# Sheet.net
KiCad netlist of a schematic drawn in Altium Designer
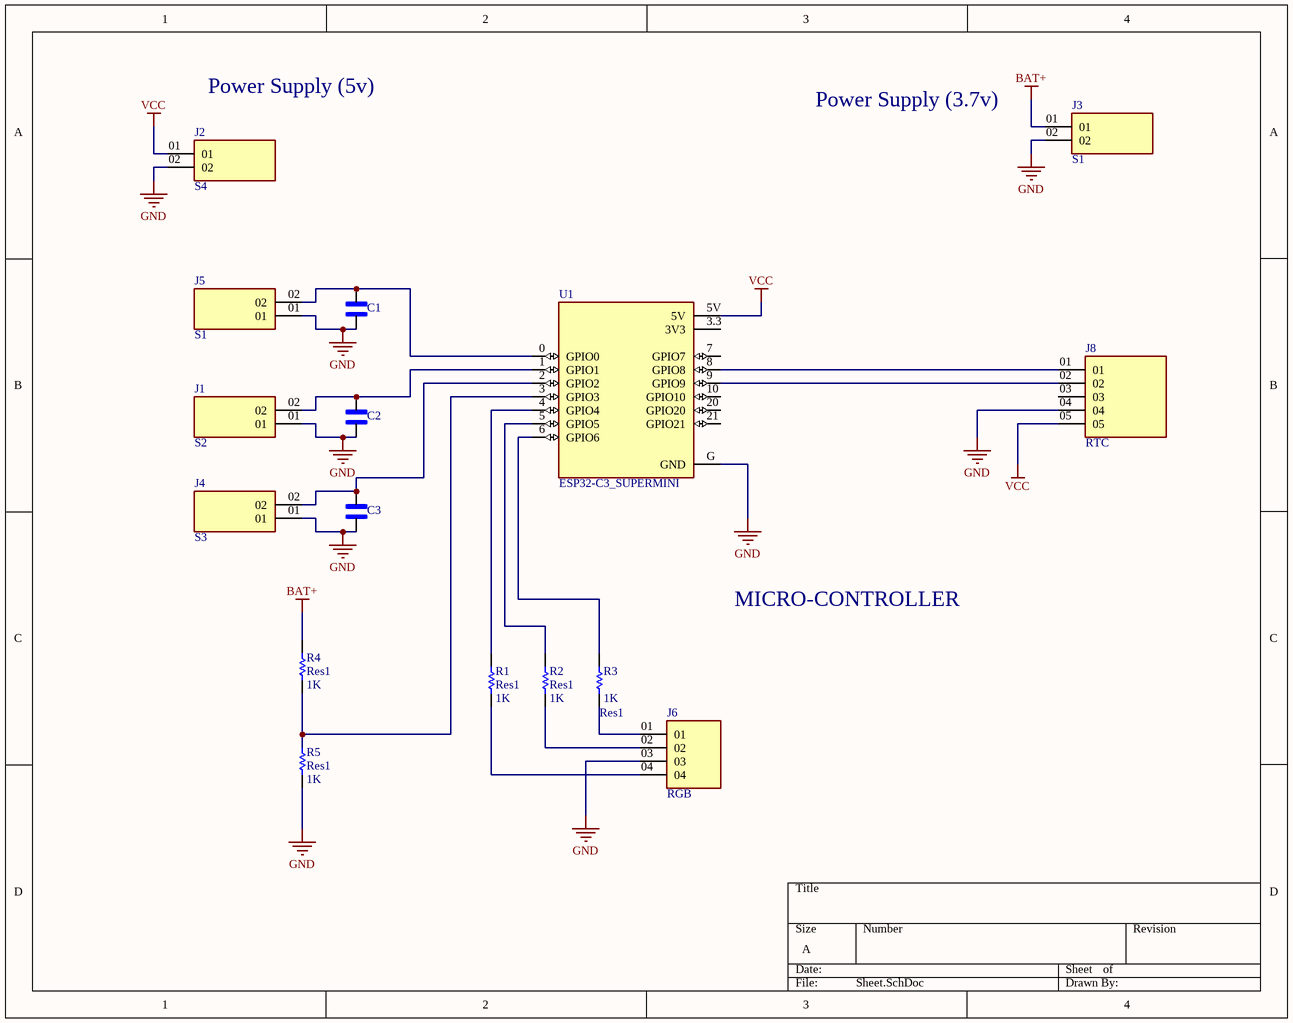
[diagram p0: Sheet.SchDoc]

(export (version "E")
  (design (tool "Eeschema 10.0.6"))
  (components
    (comp (ref "C1")
      (value "C315C470J1G5TA")
      (footprint "CAPRR254W54L381T254H466")
      (description "Capacitor: ceramic; MLCC, monolithic; 47pF; 100V; C0G; Â±5%; THT")
      (fields (field (name "MF") "KEMET"))
      (libsource (lib "C315C470J1G5TA") (part "C315C470J1G5TA"))
    )
    (comp (ref "C2")
      (value "C315C470J1G5TA")
      (footprint "CAPRR254W54L381T254H466")
      (description "Capacitor: ceramic; MLCC, monolithic; 47pF; 100V; C0G; Â±5%; THT")
      (fields (field (name "MF") "KEMET"))
      (libsource (lib "C315C470J1G5TA") (part "C315C470J1G5TA"))
    )
    (comp (ref "C3")
      (value "C315C470J1G5TA")
      (footprint "CAPRR254W54L381T254H466")
      (description "Capacitor: ceramic; MLCC, monolithic; 47pF; 100V; C0G; Â±5%; THT")
      (fields (field (name "MF") "KEMET"))
      (libsource (lib "C315C470J1G5TA") (part "C315C470J1G5TA"))
    )
    (comp (ref "J1")
      (value "S2")
      (footprint "SAMTEC_TSW-202-07-T-S:SAMTEC_TSW-202-07-T-S")
      (fields (field (name "MP") "TSW-202-07-T-S"))
      (libsource (lib "TSW-202-07-T-S") (part "TSW-202-07-T-S"))
    )
    (comp (ref "J2")
      (value "S4")
      (footprint "SAMTEC_TSW-202-07-T-S:SAMTEC_TSW-202-07-T-S")
      (fields (field (name "MP") "TSW-202-07-T-S"))
      (libsource (lib "") (part "TSW-202-07-T-S_1"))
    )
    (comp (ref "J3")
      (value "S1")
      (footprint "SAMTEC_TSW-202-07-T-S:SAMTEC_TSW-202-07-T-S")
      (fields (field (name "MP") "TSW-202-07-T-S"))
      (libsource (lib "") (part "TSW-202-07-T-S_1"))
    )
    (comp (ref "J4")
      (value "S3")
      (footprint "SAMTEC_TSW-202-07-T-S:SAMTEC_TSW-202-07-T-S")
      (fields (field (name "MP") "TSW-202-07-T-S"))
      (libsource (lib "TSW-202-07-T-S") (part "TSW-202-07-T-S"))
    )
    (comp (ref "J5")
      (value "S1")
      (footprint "SAMTEC_TSW-202-07-T-S:SAMTEC_TSW-202-07-T-S")
      (fields (field (name "MP") "TSW-202-07-T-S"))
      (libsource (lib "TSW-202-07-T-S") (part "TSW-202-07-T-S"))
    )
    (comp (ref "J6")
      (value "RGB")
      (footprint "SAMTEC_MTLW-104-X-X-S-X")
      (fields (field (name "MF") "{'manufacturer': u'Samtec Inc.'}") (field (name "MP") "MTLW-104-X-X-S-X"))
      (libsource (lib "MTLW-104-X-X-S-X") (part "MTLW-104-X-X-S-X"))
    )
    (comp (ref "J8")
      (value "RTC")
      (footprint "SAMTEC_TSW-105-23-L-S")
      (description "Connector Header Through Hole 5 position 0.100 (2.54mm)")
      (fields (field (name "MF") "Samtec") (field (name "MP") "TSW-105-23-L-S"))
      (libsource (lib "TSW-105-23-L-S") (part "TSW-105-23-L-S"))
    )
    (comp (ref "R1")
      (value "Res1")
      (footprint "AXIAL-0.3")
      (description "Resistor")
      (fields (field (name "ALTIUM_VALUE") "1K") (field (name "PUBLISHER") "Altium Limited"))
      (libsource (lib "Miscellaneous Devices") (part "Res1"))
    )
    (comp (ref "R2")
      (value "Res1")
      (footprint "AXIAL-0.3")
      (description "Resistor")
      (fields (field (name "ALTIUM_VALUE") "1K") (field (name "PUBLISHER") "Altium Limited"))
      (libsource (lib "Miscellaneous Devices") (part "Res1"))
    )
    (comp (ref "R3")
      (value "Res1")
      (footprint "AXIAL-0.3")
      (description "Resistor")
      (fields (field (name "ALTIUM_VALUE") "1K") (field (name "PUBLISHER") "Altium Limited"))
      (libsource (lib "Miscellaneous Devices") (part "Res1"))
    )
    (comp (ref "R4")
      (value "Res1")
      (footprint "AXIAL-0.3")
      (description "Resistor")
      (fields (field (name "ALTIUM_VALUE") "1K") (field (name "PUBLISHER") "Altium Limited"))
      (libsource (lib "Miscellaneous Devices") (part "Res1"))
    )
    (comp (ref "R5")
      (value "Res1")
      (footprint "AXIAL-0.3")
      (description "Resistor")
      (fields (field (name "ALTIUM_VALUE") "1K") (field (name "PUBLISHER") "Altium Limited"))
      (libsource (lib "Miscellaneous Devices") (part "Res1"))
    )
    (comp (ref "U1")
      (value "ESP32-C3_SUPERMINI")
      (footprint "MODULE_ESP32-C3_SUPERMINI")
      (description "Super tiny ESP32-C3 board")
      (fields (field (name "MF") "Espressif Systems") (field (name "MP") "ESP32-C3 SuperMini"))
      (libsource (lib "ESP32-C3_SUPERMINI") (part "ESP32-C3_SUPERMINI"))
    )
  )
  (nets
    (net (code "1") (name "BAT+") (class "Default")
      (node (ref "J3") (pin "01") (pinfunction "01_01") (pintype "passive"))
      (node (ref "R4") (pin "1") (pinfunction "1_1") (pintype "passive"))
    )
    (net (code "2") (name "GND") (class "Default")
      (node (ref "C1") (pin "1") (pinfunction "1_1") (pintype "passive"))
      (node (ref "C2") (pin "1") (pinfunction "1_1") (pintype "passive"))
      (node (ref "C3") (pin "1") (pinfunction "1_1") (pintype "passive"))
      (node (ref "J1") (pin "01") (pinfunction "01_01") (pintype "passive"))
      (node (ref "J2") (pin "02") (pinfunction "02_02") (pintype "passive"))
      (node (ref "J3") (pin "02") (pinfunction "02_02") (pintype "passive"))
      (node (ref "J4") (pin "01") (pinfunction "01_01") (pintype "passive"))
      (node (ref "J5") (pin "01") (pinfunction "01_01") (pintype "passive"))
      (node (ref "J6") (pin "03") (pinfunction "03_03") (pintype "passive"))
      (node (ref "J8") (pin "04") (pinfunction "04_04") (pintype "passive"))
      (node (ref "R5") (pin "2") (pinfunction "2_2") (pintype "passive"))
      (node (ref "U1") (pin "G") (pinfunction "GND_G") (pintype "power_in"))
    )
    (net (code "3") (name "Net-(J6-Pad01)") (class "Default")
      (node (ref "J6") (pin "01") (pinfunction "01_01") (pintype "passive"))
      (node (ref "R3") (pin "2") (pinfunction "2_2") (pintype "passive"))
    )
    (net (code "4") (name "Net-(J6-Pad02)") (class "Default")
      (node (ref "J6") (pin "02") (pinfunction "02_02") (pintype "passive"))
      (node (ref "R2") (pin "2") (pinfunction "2_2") (pintype "passive"))
    )
    (net (code "5") (name "Net-(J6-Pad04)") (class "Default")
      (node (ref "J6") (pin "04") (pinfunction "04_04") (pintype "passive"))
      (node (ref "R1") (pin "2") (pinfunction "2_2") (pintype "passive"))
    )
    (net (code "6") (name "Net-(U1-GPIO0)") (class "Default")
      (node (ref "C1") (pin "2") (pinfunction "2_2") (pintype "passive"))
      (node (ref "J5") (pin "02") (pinfunction "02_02") (pintype "passive"))
      (node (ref "U1") (pin "0") (pinfunction "GPIO0_0") (pintype "bidirectional"))
    )
    (net (code "7") (name "Net-(U1-GPIO1)") (class "Default")
      (node (ref "C2") (pin "2") (pinfunction "2_2") (pintype "passive"))
      (node (ref "J1") (pin "02") (pinfunction "02_02") (pintype "passive"))
      (node (ref "U1") (pin "1") (pinfunction "GPIO1_1") (pintype "bidirectional"))
    )
    (net (code "8") (name "Net-(U1-GPIO2)") (class "Default")
      (node (ref "C3") (pin "2") (pinfunction "2_2") (pintype "passive"))
      (node (ref "J4") (pin "02") (pinfunction "02_02") (pintype "passive"))
      (node (ref "U1") (pin "2") (pinfunction "GPIO2_2") (pintype "bidirectional"))
    )
    (net (code "9") (name "Net-(U1-GPIO3)") (class "Default")
      (node (ref "R4") (pin "2") (pinfunction "2_2") (pintype "passive"))
      (node (ref "R5") (pin "1") (pinfunction "1_1") (pintype "passive"))
      (node (ref "U1") (pin "3") (pinfunction "GPIO3_3") (pintype "bidirectional"))
    )
    (net (code "10") (name "Net-(U1-GPIO4)") (class "Default")
      (node (ref "R1") (pin "1") (pinfunction "1_1") (pintype "passive"))
      (node (ref "U1") (pin "4") (pinfunction "GPIO4_4") (pintype "bidirectional"))
    )
    (net (code "11") (name "Net-(U1-GPIO5)") (class "Default")
      (node (ref "R2") (pin "1") (pinfunction "1_1") (pintype "passive"))
      (node (ref "U1") (pin "5") (pinfunction "GPIO5_5") (pintype "bidirectional"))
    )
    (net (code "12") (name "Net-(U1-GPIO6)") (class "Default")
      (node (ref "R3") (pin "1") (pinfunction "1_1") (pintype "passive"))
      (node (ref "U1") (pin "6") (pinfunction "GPIO6_6") (pintype "bidirectional"))
    )
    (net (code "13") (name "Net-(U1-GPIO8)") (class "Default")
      (node (ref "J8") (pin "01") (pinfunction "01_01") (pintype "passive"))
      (node (ref "U1") (pin "8") (pinfunction "GPIO8_8") (pintype "bidirectional"))
    )
    (net (code "14") (name "Net-(U1-GPIO9)") (class "Default")
      (node (ref "J8") (pin "02") (pinfunction "02_02") (pintype "passive"))
      (node (ref "U1") (pin "9") (pinfunction "GPIO9_9") (pintype "bidirectional"))
    )
    (net (code "15") (name "VCC") (class "Default")
      (node (ref "J2") (pin "01") (pinfunction "01_01") (pintype "passive"))
      (node (ref "J8") (pin "05") (pinfunction "05_05") (pintype "passive"))
      (node (ref "U1") (pin "5V") (pinfunction "5V_5V") (pintype "power_in"))
    )
    (net (code "16") (name "unconnected-(J8-Pad03)") (class "Default")
      (node (ref "J8") (pin "03") (pinfunction "03_03") (pintype "passive"))
    )
    (net (code "17") (name "unconnected-(U1-3V3-Pad3.3)") (class "Default")
      (node (ref "U1") (pin "3.3") (pinfunction "3V3_3.3") (pintype "power_in"))
    )
    (net (code "18") (name "unconnected-(U1-GPIO7-Pad7)") (class "Default")
      (node (ref "U1") (pin "7") (pinfunction "GPIO7_7") (pintype "bidirectional"))
    )
    (net (code "19") (name "unconnected-(U1-GPIO10-Pad10)") (class "Default")
      (node (ref "U1") (pin "10") (pinfunction "GPIO10_10") (pintype "bidirectional"))
    )
    (net (code "20") (name "unconnected-(U1-GPIO20-Pad20)") (class "Default")
      (node (ref "U1") (pin "20") (pinfunction "GPIO20_20") (pintype "bidirectional"))
    )
    (net (code "21") (name "unconnected-(U1-GPIO21-Pad21)") (class "Default")
      (node (ref "U1") (pin "21") (pinfunction "GPIO21_21") (pintype "bidirectional"))
    )
  )
)
